# PSU2.net
KiCad netlist of a schematic drawn in Altium Designer
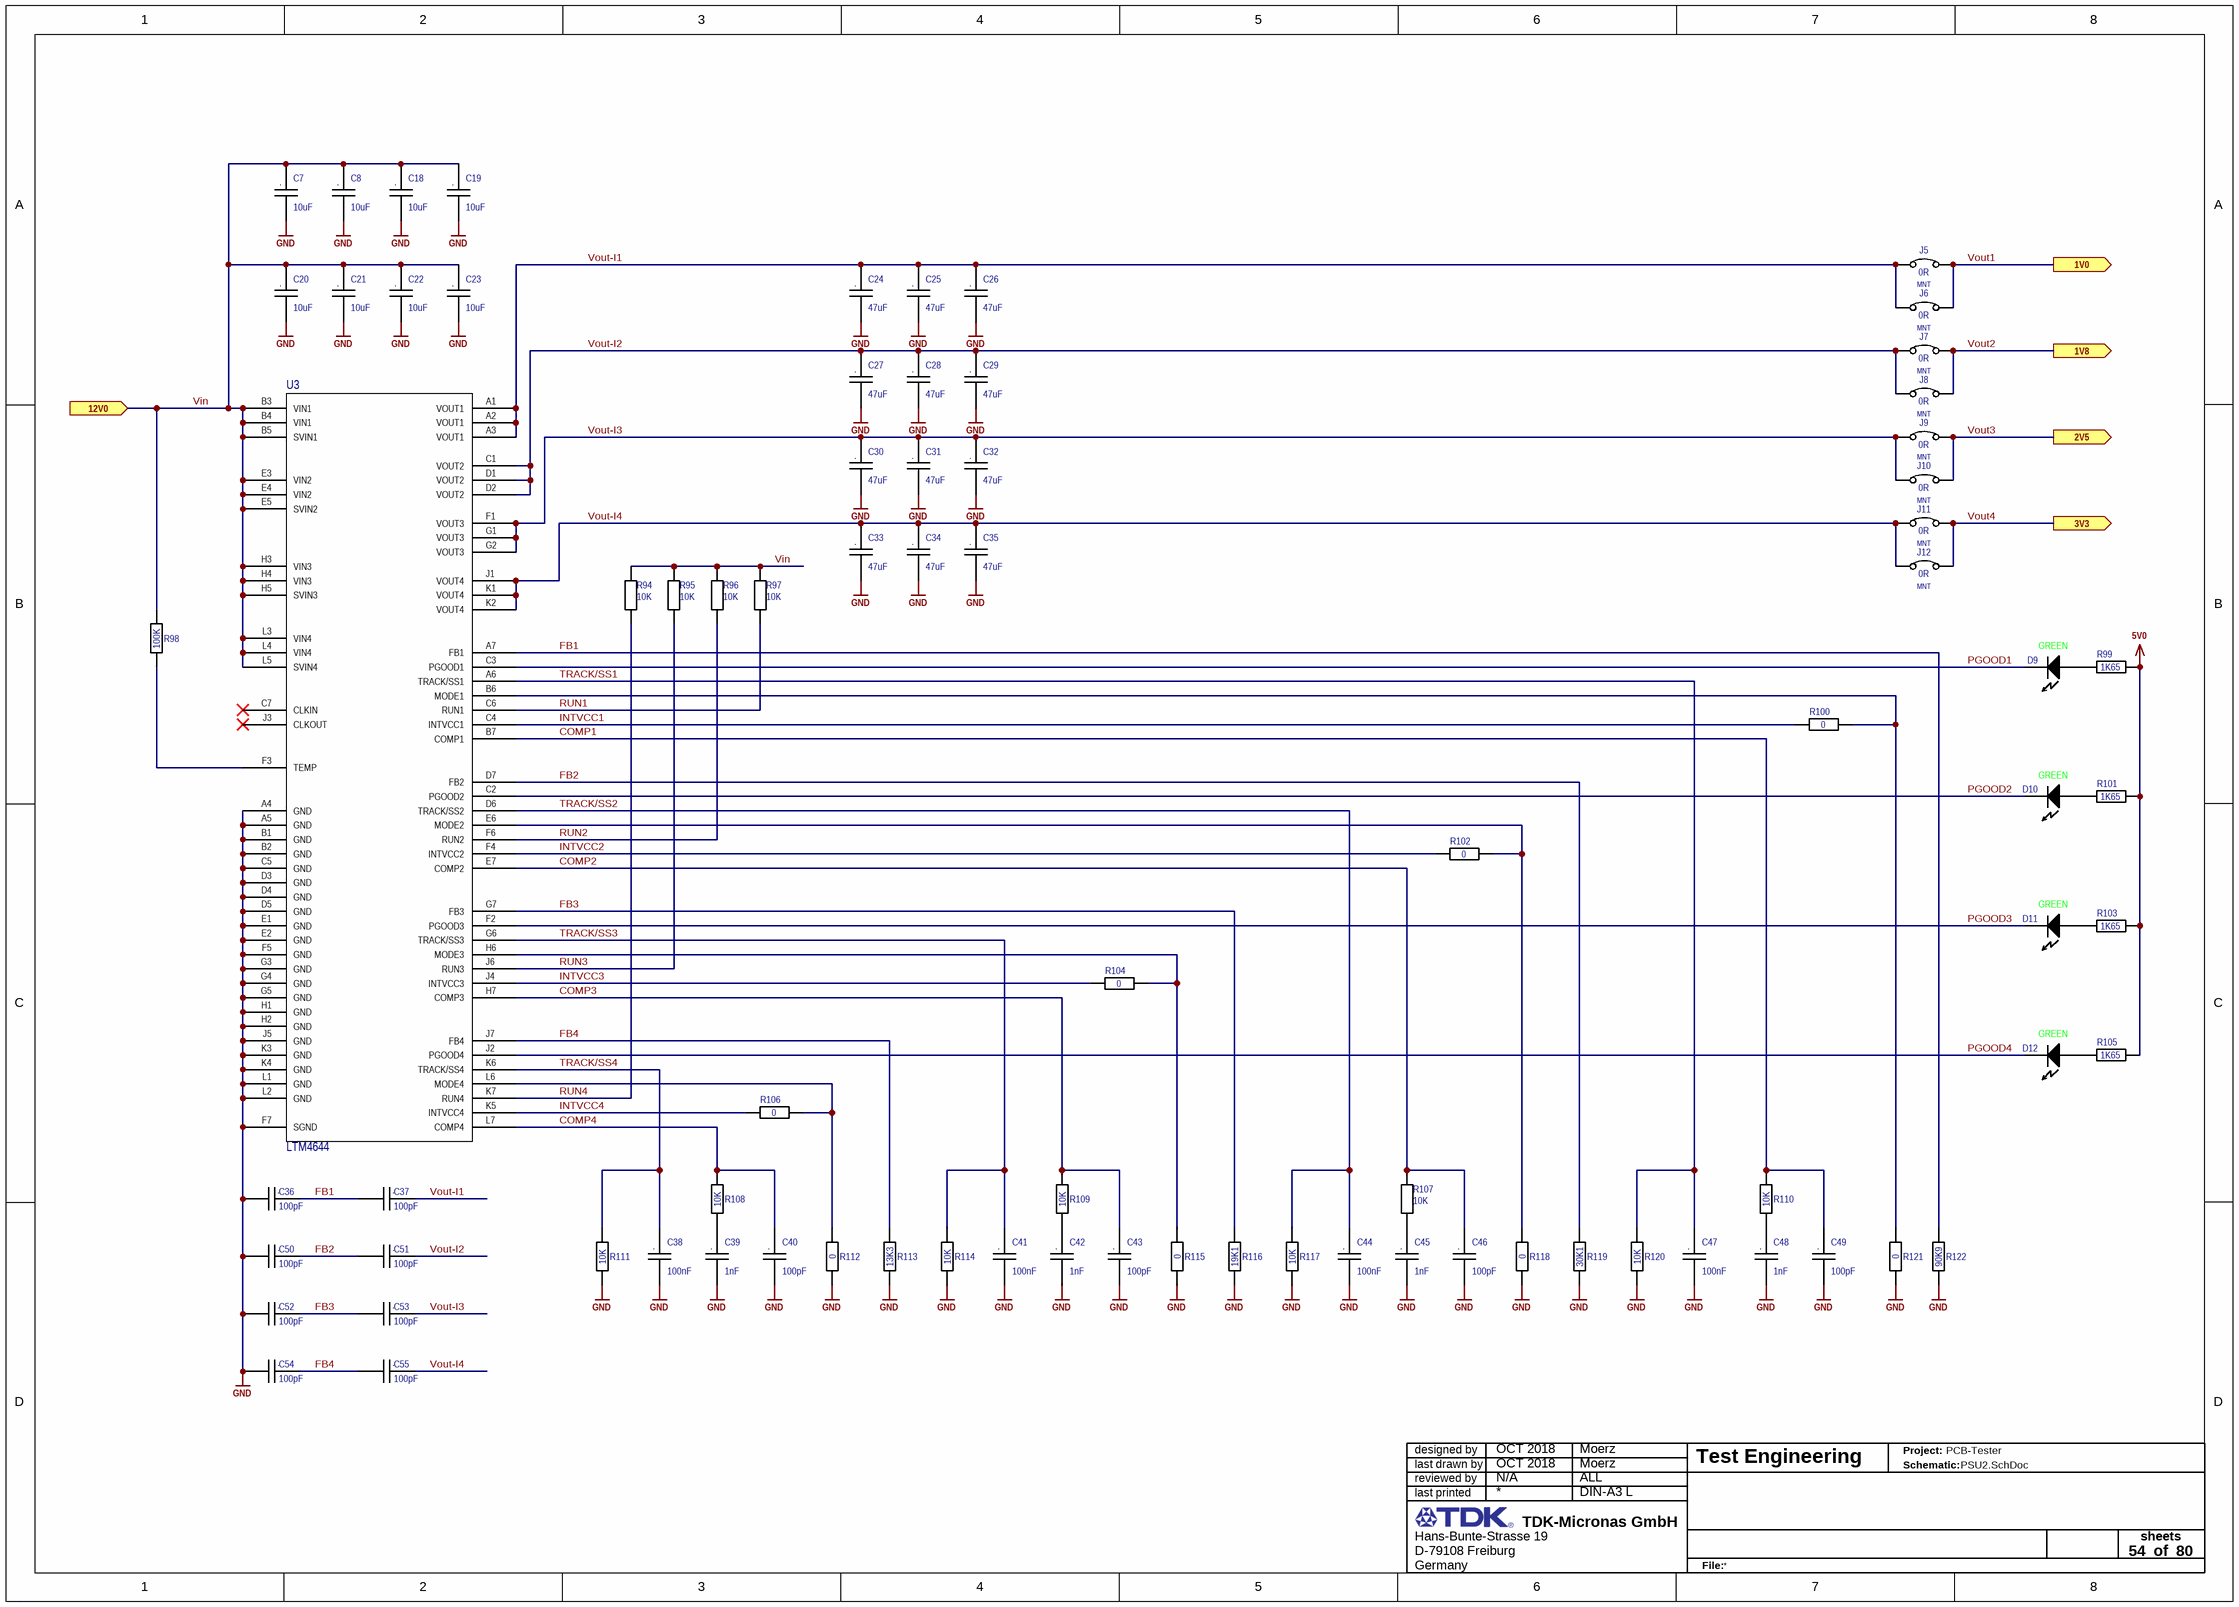
[diagram p0: PSU2.SchDoc]

(export (version "E")
  (design (tool "Eeschema 10.0.6"))
  (components
    (comp (ref "C7")
      (value "10uF")
      (footprint "C1206 Reflow")
      (description "CAP CER 10UF 25V X7R 1206")
      (fields
        (field (name "TOLERANCE") "±10%")
        (field (name "02. DISTRIBUTOR PART NUMBER") "445-7705-6-ND")
        (field (name "13. CREATED DATE/NAME") "AUG2018/Hören")
      )
      (libsource (lib "chickenfood") (part "C"))
    )
    (comp (ref "C8")
      (value "10uF")
      (footprint "C1206 Reflow")
      (description "CAP CER 10UF 25V X7R 1206")
      (fields
        (field (name "TOLERANCE") "±10%")
        (field (name "02. DISTRIBUTOR PART NUMBER") "445-7705-6-ND")
        (field (name "13. CREATED DATE/NAME") "AUG2018/Hören")
      )
      (libsource (lib "chickenfood") (part "C"))
    )
    (comp (ref "C18")
      (value "10uF")
      (footprint "C1206 Reflow")
      (description "CAP CER 10UF 25V X7R 1206")
      (fields
        (field (name "TOLERANCE") "±10%")
        (field (name "02. DISTRIBUTOR PART NUMBER") "445-7705-6-ND")
        (field (name "13. CREATED DATE/NAME") "AUG2018/Hören")
      )
      (libsource (lib "chickenfood") (part "C"))
    )
    (comp (ref "C19")
      (value "10uF")
      (footprint "C1206 Reflow")
      (description "CAP CER 10UF 25V X7R 1206")
      (fields
        (field (name "TOLERANCE") "±10%")
        (field (name "02. DISTRIBUTOR PART NUMBER") "445-7705-6-ND")
        (field (name "13. CREATED DATE/NAME") "AUG2018/Hören")
      )
      (libsource (lib "chickenfood") (part "C"))
    )
    (comp (ref "C20")
      (value "10uF")
      (footprint "C1206 Reflow")
      (description "CAP CER 10UF 25V X7R 1206")
      (fields
        (field (name "TOLERANCE") "±10%")
        (field (name "02. DISTRIBUTOR PART NUMBER") "445-7705-6-ND")
        (field (name "13. CREATED DATE/NAME") "AUG2018/Hören")
      )
      (libsource (lib "chickenfood") (part "C"))
    )
    (comp (ref "C21")
      (value "10uF")
      (footprint "C1206 Reflow")
      (description "CAP CER 10UF 25V X7R 1206")
      (fields
        (field (name "TOLERANCE") "±10%")
        (field (name "02. DISTRIBUTOR PART NUMBER") "445-7705-6-ND")
        (field (name "13. CREATED DATE/NAME") "AUG2018/Hören")
      )
      (libsource (lib "chickenfood") (part "C"))
    )
    (comp (ref "C22")
      (value "10uF")
      (footprint "C1206 Reflow")
      (description "CAP CER 10UF 25V X7R 1206")
      (fields
        (field (name "TOLERANCE") "±10%")
        (field (name "02. DISTRIBUTOR PART NUMBER") "445-7705-6-ND")
        (field (name "13. CREATED DATE/NAME") "AUG2018/Hören")
      )
      (libsource (lib "chickenfood") (part "C"))
    )
    (comp (ref "C23")
      (value "10uF")
      (footprint "C1206 Reflow")
      (description "CAP CER 10UF 25V X7R 1206")
      (fields
        (field (name "TOLERANCE") "±10%")
        (field (name "02. DISTRIBUTOR PART NUMBER") "445-7705-6-ND")
        (field (name "13. CREATED DATE/NAME") "AUG2018/Hören")
      )
      (libsource (lib "chickenfood") (part "C"))
    )
    (comp (ref "C24")
      (value "47uF")
      (footprint "C1210 Reflow")
      (description "CAP CER 47UF 10V X5R 1210")
      (fields
        (field (name "TOLERANCE") "±20%")
        (field (name "02. DISTRIBUTOR PART NUMBER") "1276-3380-6-ND")
        (field (name "13. CREATED DATE/NAME") "AUG2018/Hören")
      )
      (libsource (lib "chickenfood") (part "C"))
    )
    (comp (ref "C25")
      (value "47uF")
      (footprint "C1210 Reflow")
      (description "CAP CER 47UF 10V X5R 1210")
      (fields
        (field (name "TOLERANCE") "±20%")
        (field (name "02. DISTRIBUTOR PART NUMBER") "1276-3380-6-ND")
        (field (name "13. CREATED DATE/NAME") "AUG2018/Hören")
      )
      (libsource (lib "chickenfood") (part "C"))
    )
    (comp (ref "C26")
      (value "47uF")
      (footprint "C1210 Reflow")
      (description "CAP CER 47UF 10V X5R 1210")
      (fields
        (field (name "TOLERANCE") "±20%")
        (field (name "02. DISTRIBUTOR PART NUMBER") "1276-3380-6-ND")
        (field (name "13. CREATED DATE/NAME") "AUG2018/Hören")
      )
      (libsource (lib "chickenfood") (part "C"))
    )
    (comp (ref "C27")
      (value "47uF")
      (footprint "C1210 Reflow")
      (description "CAP CER 47UF 10V X5R 1210")
      (fields
        (field (name "TOLERANCE") "±20%")
        (field (name "02. DISTRIBUTOR PART NUMBER") "1276-3380-6-ND")
        (field (name "13. CREATED DATE/NAME") "AUG2018/Hören")
      )
      (libsource (lib "chickenfood") (part "C"))
    )
    (comp (ref "C28")
      (value "47uF")
      (footprint "C1210 Reflow")
      (description "CAP CER 47UF 10V X5R 1210")
      (fields
        (field (name "TOLERANCE") "±20%")
        (field (name "02. DISTRIBUTOR PART NUMBER") "1276-3380-6-ND")
        (field (name "13. CREATED DATE/NAME") "AUG2018/Hören")
      )
      (libsource (lib "chickenfood") (part "C"))
    )
    (comp (ref "C29")
      (value "47uF")
      (footprint "C1210 Reflow")
      (description "CAP CER 47UF 10V X5R 1210")
      (fields
        (field (name "TOLERANCE") "±20%")
        (field (name "02. DISTRIBUTOR PART NUMBER") "1276-3380-6-ND")
        (field (name "13. CREATED DATE/NAME") "AUG2018/Hören")
      )
      (libsource (lib "chickenfood") (part "C"))
    )
    (comp (ref "C30")
      (value "47uF")
      (footprint "C1210 Reflow")
      (description "CAP CER 47UF 10V X5R 1210")
      (fields
        (field (name "TOLERANCE") "±20%")
        (field (name "02. DISTRIBUTOR PART NUMBER") "1276-3380-6-ND")
        (field (name "13. CREATED DATE/NAME") "AUG2018/Hören")
      )
      (libsource (lib "chickenfood") (part "C"))
    )
    (comp (ref "C31")
      (value "47uF")
      (footprint "C1210 Reflow")
      (description "CAP CER 47UF 10V X5R 1210")
      (fields
        (field (name "TOLERANCE") "±20%")
        (field (name "02. DISTRIBUTOR PART NUMBER") "1276-3380-6-ND")
        (field (name "13. CREATED DATE/NAME") "AUG2018/Hören")
      )
      (libsource (lib "chickenfood") (part "C"))
    )
    (comp (ref "C32")
      (value "47uF")
      (footprint "C1210 Reflow")
      (description "CAP CER 47UF 10V X5R 1210")
      (fields
        (field (name "TOLERANCE") "±20%")
        (field (name "02. DISTRIBUTOR PART NUMBER") "1276-3380-6-ND")
        (field (name "13. CREATED DATE/NAME") "AUG2018/Hören")
      )
      (libsource (lib "chickenfood") (part "C"))
    )
    (comp (ref "C33")
      (value "47uF")
      (footprint "C1210 Reflow")
      (description "CAP CER 47UF 10V X5R 1210")
      (fields
        (field (name "TOLERANCE") "±20%")
        (field (name "02. DISTRIBUTOR PART NUMBER") "1276-3380-6-ND")
        (field (name "13. CREATED DATE/NAME") "AUG2018/Hören")
      )
      (libsource (lib "chickenfood") (part "C"))
    )
    (comp (ref "C34")
      (value "47uF")
      (footprint "C1210 Reflow")
      (description "CAP CER 47UF 10V X5R 1210")
      (fields
        (field (name "TOLERANCE") "±20%")
        (field (name "02. DISTRIBUTOR PART NUMBER") "1276-3380-6-ND")
        (field (name "13. CREATED DATE/NAME") "AUG2018/Hören")
      )
      (libsource (lib "chickenfood") (part "C"))
    )
    (comp (ref "C35")
      (value "47uF")
      (footprint "C1210 Reflow")
      (description "CAP CER 47UF 10V X5R 1210")
      (fields
        (field (name "TOLERANCE") "±20%")
        (field (name "02. DISTRIBUTOR PART NUMBER") "1276-3380-6-ND")
        (field (name "13. CREATED DATE/NAME") "AUG2018/Hören")
      )
      (libsource (lib "chickenfood") (part "C"))
    )
    (comp (ref "C36")
      (value "100pF")
      (footprint "C0402 Reflow")
      (description "CAP CER 100PF 25V C0G/NP0 0402")
      (fields
        (field (name "TOLERANCE") "±5%")
        (field (name "02. DISTRIBUTOR PART NUMBER") "399-1022-6-ND")
        (field (name "13. CREATED DATE/NAME") "AUG2018/Hören")
      )
      (libsource (lib "chickenfood") (part "C"))
    )
    (comp (ref "C37")
      (value "100pF")
      (footprint "C0402 Reflow")
      (description "CAP CER 100PF 25V C0G/NP0 0402")
      (fields
        (field (name "TOLERANCE") "±5%")
        (field (name "02. DISTRIBUTOR PART NUMBER") "399-1022-6-ND")
        (field (name "13. CREATED DATE/NAME") "AUG2018/Hören")
      )
      (libsource (lib "chickenfood") (part "C"))
    )
    (comp (ref "C38")
      (value "100nF")
      (footprint "C0402 Reflow")
      (description "CAP CER 0.1UF 25V X7R 0402")
      (fields
        (field (name "TOLERANCE") "±10%")
        (field (name "02. DISTRIBUTOR PART NUMBER") "311-2077-6-ND")
        (field (name "13. CREATED DATE/NAME") "AUG2018/Hören")
      )
      (libsource (lib "chickenfood") (part "C"))
    )
    (comp (ref "C39")
      (value "1nF")
      (footprint "C0402 Reflow")
      (description "CAP CER 1000PF 25V X7R 0402")
      (fields
        (field (name "TOLERANCE") "±10%")
        (field (name "02. DISTRIBUTOR PART NUMBER") "399-1031-6-ND")
        (field (name "13. CREATED DATE/NAME") "AUG2018/Hören")
      )
      (libsource (lib "chickenfood") (part "C"))
    )
    (comp (ref "C40")
      (value "100pF")
      (footprint "C0402 Reflow")
      (description "CAP CER 100PF 25V C0G/NP0 0402")
      (fields
        (field (name "TOLERANCE") "±5%")
        (field (name "02. DISTRIBUTOR PART NUMBER") "399-1022-6-ND")
        (field (name "13. CREATED DATE/NAME") "AUG2018/Hören")
      )
      (libsource (lib "chickenfood") (part "C"))
    )
    (comp (ref "C41")
      (value "100nF")
      (footprint "C0402 Reflow")
      (description "CAP CER 0.1UF 25V X7R 0402")
      (fields
        (field (name "TOLERANCE") "±10%")
        (field (name "02. DISTRIBUTOR PART NUMBER") "311-2077-6-ND")
        (field (name "13. CREATED DATE/NAME") "AUG2018/Hören")
      )
      (libsource (lib "chickenfood") (part "C"))
    )
    (comp (ref "C42")
      (value "1nF")
      (footprint "C0402 Reflow")
      (description "CAP CER 1000PF 25V X7R 0402")
      (fields
        (field (name "TOLERANCE") "±10%")
        (field (name "02. DISTRIBUTOR PART NUMBER") "399-1031-6-ND")
        (field (name "13. CREATED DATE/NAME") "AUG2018/Hören")
      )
      (libsource (lib "chickenfood") (part "C"))
    )
    (comp (ref "C43")
      (value "100pF")
      (footprint "C0402 Reflow")
      (description "CAP CER 100PF 25V C0G/NP0 0402")
      (fields
        (field (name "TOLERANCE") "±5%")
        (field (name "02. DISTRIBUTOR PART NUMBER") "399-1022-6-ND")
        (field (name "13. CREATED DATE/NAME") "AUG2018/Hören")
      )
      (libsource (lib "chickenfood") (part "C"))
    )
    (comp (ref "C44")
      (value "100nF")
      (footprint "C0402 Reflow")
      (description "CAP CER 0.1UF 25V X7R 0402")
      (fields
        (field (name "TOLERANCE") "±10%")
        (field (name "02. DISTRIBUTOR PART NUMBER") "311-2077-6-ND")
        (field (name "13. CREATED DATE/NAME") "AUG2018/Hören")
      )
      (libsource (lib "chickenfood") (part "C"))
    )
    (comp (ref "C45")
      (value "1nF")
      (footprint "C0402 Reflow")
      (description "CAP CER 1000PF 25V X7R 0402")
      (fields
        (field (name "TOLERANCE") "±10%")
        (field (name "02. DISTRIBUTOR PART NUMBER") "399-1031-6-ND")
        (field (name "13. CREATED DATE/NAME") "AUG2018/Hören")
      )
      (libsource (lib "chickenfood") (part "C"))
    )
    (comp (ref "C46")
      (value "100pF")
      (footprint "C0402 Reflow")
      (description "CAP CER 100PF 25V C0G/NP0 0402")
      (fields
        (field (name "TOLERANCE") "±5%")
        (field (name "02. DISTRIBUTOR PART NUMBER") "399-1022-6-ND")
        (field (name "13. CREATED DATE/NAME") "AUG2018/Hören")
      )
      (libsource (lib "chickenfood") (part "C"))
    )
    (comp (ref "C47")
      (value "100nF")
      (footprint "C0402 Reflow")
      (description "CAP CER 0.1UF 25V X7R 0402")
      (fields
        (field (name "TOLERANCE") "±10%")
        (field (name "02. DISTRIBUTOR PART NUMBER") "311-2077-6-ND")
        (field (name "13. CREATED DATE/NAME") "AUG2018/Hören")
      )
      (libsource (lib "chickenfood") (part "C"))
    )
    (comp (ref "C48")
      (value "1nF")
      (footprint "C0402 Reflow")
      (description "CAP CER 1000PF 25V X7R 0402")
      (fields
        (field (name "TOLERANCE") "±10%")
        (field (name "02. DISTRIBUTOR PART NUMBER") "399-1031-6-ND")
        (field (name "13. CREATED DATE/NAME") "AUG2018/Hören")
      )
      (libsource (lib "chickenfood") (part "C"))
    )
    (comp (ref "C49")
      (value "100pF")
      (footprint "C0402 Reflow")
      (description "CAP CER 100PF 25V C0G/NP0 0402")
      (fields
        (field (name "TOLERANCE") "±5%")
        (field (name "02. DISTRIBUTOR PART NUMBER") "399-1022-6-ND")
        (field (name "13. CREATED DATE/NAME") "AUG2018/Hören")
      )
      (libsource (lib "chickenfood") (part "C"))
    )
    (comp (ref "C50")
      (value "100pF")
      (footprint "C0402 Reflow")
      (description "CAP CER 100PF 25V C0G/NP0 0402")
      (fields
        (field (name "TOLERANCE") "±5%")
        (field (name "02. DISTRIBUTOR PART NUMBER") "399-1022-6-ND")
        (field (name "13. CREATED DATE/NAME") "AUG2018/Hören")
      )
      (libsource (lib "chickenfood") (part "C"))
    )
    (comp (ref "C51")
      (value "100pF")
      (footprint "C0402 Reflow")
      (description "CAP CER 100PF 25V C0G/NP0 0402")
      (fields
        (field (name "TOLERANCE") "±5%")
        (field (name "02. DISTRIBUTOR PART NUMBER") "399-1022-6-ND")
        (field (name "13. CREATED DATE/NAME") "AUG2018/Hören")
      )
      (libsource (lib "chickenfood") (part "C"))
    )
    (comp (ref "C52")
      (value "100pF")
      (footprint "C0402 Reflow")
      (description "CAP CER 100PF 25V C0G/NP0 0402")
      (fields
        (field (name "TOLERANCE") "±5%")
        (field (name "02. DISTRIBUTOR PART NUMBER") "399-1022-6-ND")
        (field (name "13. CREATED DATE/NAME") "AUG2018/Hören")
      )
      (libsource (lib "chickenfood") (part "C"))
    )
    (comp (ref "C53")
      (value "100pF")
      (footprint "C0402 Reflow")
      (description "CAP CER 100PF 25V C0G/NP0 0402")
      (fields
        (field (name "TOLERANCE") "±5%")
        (field (name "02. DISTRIBUTOR PART NUMBER") "399-1022-6-ND")
        (field (name "13. CREATED DATE/NAME") "AUG2018/Hören")
      )
      (libsource (lib "chickenfood") (part "C"))
    )
    (comp (ref "C54")
      (value "100pF")
      (footprint "C0402 Reflow")
      (description "CAP CER 100PF 25V C0G/NP0 0402")
      (fields
        (field (name "TOLERANCE") "±5%")
        (field (name "02. DISTRIBUTOR PART NUMBER") "399-1022-6-ND")
        (field (name "13. CREATED DATE/NAME") "AUG2018/Hören")
      )
      (libsource (lib "chickenfood") (part "C"))
    )
    (comp (ref "C55")
      (value "100pF")
      (footprint "C0402 Reflow")
      (description "CAP CER 100PF 25V C0G/NP0 0402")
      (fields
        (field (name "TOLERANCE") "±5%")
        (field (name "02. DISTRIBUTOR PART NUMBER") "399-1022-6-ND")
        (field (name "13. CREATED DATE/NAME") "AUG2018/Hören")
      )
      (libsource (lib "chickenfood") (part "C"))
    )
    (comp (ref "D9")
      (value "D")
      (footprint "L0603G")
      (description "LED GREEN DIFFUSED 0603 SMD")
      (fields
        (field (name "02. DISTRIBUTOR PART NUMBER") "475-2709-6-ND")
        (field (name "07. MANUFACTURER  PART NUMBER") "LG L29K-G2J1-24-Z")
        (field (name "COLOR") "GREEN")
        (field (name "13. CREATED DATE/NAME") "AUG2018/Hören")
      )
      (libsource (lib "chickenfood") (part "LED"))
    )
    (comp (ref "D10")
      (value "D")
      (footprint "L0603G")
      (description "LED GREEN DIFFUSED 0603 SMD")
      (fields
        (field (name "02. DISTRIBUTOR PART NUMBER") "475-2709-6-ND")
        (field (name "07. MANUFACTURER  PART NUMBER") "LG L29K-G2J1-24-Z")
        (field (name "COLOR") "GREEN")
        (field (name "13. CREATED DATE/NAME") "AUG2018/Hören")
      )
      (libsource (lib "chickenfood") (part "LED"))
    )
    (comp (ref "D11")
      (value "D")
      (footprint "L0603G")
      (description "LED GREEN DIFFUSED 0603 SMD")
      (fields
        (field (name "02. DISTRIBUTOR PART NUMBER") "475-2709-6-ND")
        (field (name "07. MANUFACTURER  PART NUMBER") "LG L29K-G2J1-24-Z")
        (field (name "COLOR") "GREEN")
        (field (name "13. CREATED DATE/NAME") "AUG2018/Hören")
      )
      (libsource (lib "chickenfood") (part "LED"))
    )
    (comp (ref "D12")
      (value "D")
      (footprint "L0603G")
      (description "LED GREEN DIFFUSED 0603 SMD")
      (fields
        (field (name "02. DISTRIBUTOR PART NUMBER") "475-2709-6-ND")
        (field (name "07. MANUFACTURER  PART NUMBER") "LG L29K-G2J1-24-Z")
        (field (name "COLOR") "GREEN")
        (field (name "13. CREATED DATE/NAME") "AUG2018/Hören")
      )
      (libsource (lib "chickenfood") (part "LED"))
    )
    (comp (ref "J5")
      (value "0R")
      (footprint "JumperSMD")
      (description "RES SMD 0 OHM JUMPER 1/10W 0603")
      (fields
        (field (name "02. DISTRIBUTOR PART NUMBER") "311-0.0GRDKR-ND")
        (field (name "07. MANUFACTURER  PART NUMBER") "RC0603JR-070RL")
        (field (name "POPULATED") "MNT")
      )
      (libsource (lib "chickenfood") (part "Jumper SMD"))
    )
    (comp (ref "J6")
      (value "0R")
      (footprint "JumperSMD")
      (description "RES SMD 0 OHM JUMPER 1/10W 0603")
      (fields
        (field (name "02. DISTRIBUTOR PART NUMBER") "311-0.0GRDKR-ND")
        (field (name "07. MANUFACTURER  PART NUMBER") "RC0603JR-070RL")
        (field (name "POPULATED") "MNT")
      )
      (libsource (lib "chickenfood") (part "Jumper SMD"))
    )
    (comp (ref "J7")
      (value "0R")
      (footprint "JumperSMD")
      (description "RES SMD 0 OHM JUMPER 1/10W 0603")
      (fields
        (field (name "02. DISTRIBUTOR PART NUMBER") "311-0.0GRDKR-ND")
        (field (name "07. MANUFACTURER  PART NUMBER") "RC0603JR-070RL")
        (field (name "POPULATED") "MNT")
      )
      (libsource (lib "chickenfood") (part "Jumper SMD"))
    )
    (comp (ref "J8")
      (value "0R")
      (footprint "JumperSMD")
      (description "RES SMD 0 OHM JUMPER 1/10W 0603")
      (fields
        (field (name "02. DISTRIBUTOR PART NUMBER") "311-0.0GRDKR-ND")
        (field (name "07. MANUFACTURER  PART NUMBER") "RC0603JR-070RL")
        (field (name "POPULATED") "MNT")
      )
      (libsource (lib "chickenfood") (part "Jumper SMD"))
    )
    (comp (ref "J9")
      (value "0R")
      (footprint "JumperSMD")
      (description "RES SMD 0 OHM JUMPER 1/10W 0603")
      (fields
        (field (name "02. DISTRIBUTOR PART NUMBER") "311-0.0GRDKR-ND")
        (field (name "07. MANUFACTURER  PART NUMBER") "RC0603JR-070RL")
        (field (name "POPULATED") "MNT")
      )
      (libsource (lib "chickenfood") (part "Jumper SMD"))
    )
    (comp (ref "J10")
      (value "0R")
      (footprint "JumperSMD")
      (description "RES SMD 0 OHM JUMPER 1/10W 0603")
      (fields
        (field (name "02. DISTRIBUTOR PART NUMBER") "311-0.0GRDKR-ND")
        (field (name "07. MANUFACTURER  PART NUMBER") "RC0603JR-070RL")
        (field (name "POPULATED") "MNT")
      )
      (libsource (lib "chickenfood") (part "Jumper SMD"))
    )
    (comp (ref "J11")
      (value "0R")
      (footprint "JumperSMD")
      (description "RES SMD 0 OHM JUMPER 1/10W 0603")
      (fields
        (field (name "02. DISTRIBUTOR PART NUMBER") "311-0.0GRDKR-ND")
        (field (name "07. MANUFACTURER  PART NUMBER") "RC0603JR-070RL")
        (field (name "POPULATED") "MNT")
      )
      (libsource (lib "chickenfood") (part "Jumper SMD"))
    )
    (comp (ref "J12")
      (value "0R")
      (footprint "JumperSMD")
      (description "RES SMD 0 OHM JUMPER 1/10W 0603")
      (fields
        (field (name "02. DISTRIBUTOR PART NUMBER") "311-0.0GRDKR-ND")
        (field (name "07. MANUFACTURER  PART NUMBER") "RC0603JR-070RL")
        (field (name "POPULATED") "MNT")
      )
      (libsource (lib "chickenfood") (part "Jumper SMD"))
    )
    (comp (ref "R94")
      (value "10K")
      (footprint "R0402 Reflow")
      (description "RES SMD 10K OHM 1% 1/16W 0402")
      (fields
        (field (name "TOLERANCE") "±1%")
        (field (name "02. DISTRIBUTOR PART NUMBER") "311-10.0KLRDKR-ND")
        (field (name "13. CREATED DATE/NAME") "AUG2018/Hören")
      )
      (libsource (lib "chickenfood") (part "R"))
    )
    (comp (ref "R95")
      (value "10K")
      (footprint "R0402 Reflow")
      (description "RES SMD 10K OHM 1% 1/16W 0402")
      (fields
        (field (name "TOLERANCE") "±1%")
        (field (name "02. DISTRIBUTOR PART NUMBER") "311-10.0KLRDKR-ND")
        (field (name "13. CREATED DATE/NAME") "AUG2018/Hören")
      )
      (libsource (lib "chickenfood") (part "R"))
    )
    (comp (ref "R96")
      (value "10K")
      (footprint "R0402 Reflow")
      (description "RES SMD 10K OHM 1% 1/16W 0402")
      (fields
        (field (name "TOLERANCE") "±1%")
        (field (name "02. DISTRIBUTOR PART NUMBER") "311-10.0KLRDKR-ND")
        (field (name "13. CREATED DATE/NAME") "AUG2018/Hören")
      )
      (libsource (lib "chickenfood") (part "R"))
    )
    (comp (ref "R97")
      (value "10K")
      (footprint "R0402 Reflow")
      (description "RES SMD 10K OHM 1% 1/16W 0402")
      (fields
        (field (name "TOLERANCE") "±1%")
        (field (name "02. DISTRIBUTOR PART NUMBER") "311-10.0KLRDKR-ND")
        (field (name "13. CREATED DATE/NAME") "AUG2018/Hören")
      )
      (libsource (lib "chickenfood") (part "R"))
    )
    (comp (ref "R98")
      (value "100K")
      (footprint "R0402 Reflow")
      (description "RES SMD 100K OHM 1% 1/16W 0402")
      (fields
        (field (name "TOLERANCE") "±1%")
        (field (name "02. DISTRIBUTOR PART NUMBER") "311-100KLRDKR-ND")
        (field (name "13. CREATED DATE/NAME") "AUG2018/Hören")
      )
      (libsource (lib "chickenfood") (part "R"))
    )
    (comp (ref "R99")
      (value "1K65")
      (footprint "R0402 Reflow")
      (description "RES SMD 1.65K OHM 1% 1/16W 0402")
      (fields
        (field (name "TOLERANCE") "±1%")
        (field (name "02. DISTRIBUTOR PART NUMBER") "YAG3043DKR-ND")
        (field (name "13. CREATED DATE/NAME") "AUG2018/Hören")
      )
      (libsource (lib "") (part "R_1"))
    )
    (comp (ref "R100")
      (value "0")
      (footprint "R0402 Reflow")
      (description "RES SMD 0 OHM JUMPER 1/16W 0402")
      (fields
        (field (name "02. DISTRIBUTOR PART NUMBER") "311-0.0JRDKR-ND")
        (field (name "07. MANUFACTURER  PART NUMBER") "RC0402JR-070RL")
        (field (name "13. CREATED DATE/NAME") "AUG2018/Hören")
      )
      (libsource (lib "") (part "R_2"))
    )
    (comp (ref "R101")
      (value "1K65")
      (footprint "R0402 Reflow")
      (description "RES SMD 1.65K OHM 1% 1/16W 0402")
      (fields
        (field (name "TOLERANCE") "±1%")
        (field (name "02. DISTRIBUTOR PART NUMBER") "YAG3043DKR-ND")
        (field (name "13. CREATED DATE/NAME") "AUG2018/Hören")
      )
      (libsource (lib "") (part "R_1"))
    )
    (comp (ref "R102")
      (value "0")
      (footprint "R0402 Reflow")
      (description "RES SMD 0 OHM JUMPER 1/16W 0402")
      (fields
        (field (name "02. DISTRIBUTOR PART NUMBER") "311-0.0JRDKR-ND")
        (field (name "07. MANUFACTURER  PART NUMBER") "RC0402JR-070RL")
        (field (name "13. CREATED DATE/NAME") "AUG2018/Hören")
      )
      (libsource (lib "") (part "R_2"))
    )
    (comp (ref "R103")
      (value "1K65")
      (footprint "R0402 Reflow")
      (description "RES SMD 1.65K OHM 1% 1/16W 0402")
      (fields
        (field (name "TOLERANCE") "±1%")
        (field (name "02. DISTRIBUTOR PART NUMBER") "YAG3043DKR-ND")
        (field (name "13. CREATED DATE/NAME") "AUG2018/Hören")
      )
      (libsource (lib "") (part "R_1"))
    )
    (comp (ref "R104")
      (value "0")
      (footprint "R0402 Reflow")
      (description "RES SMD 0 OHM JUMPER 1/16W 0402")
      (fields
        (field (name "02. DISTRIBUTOR PART NUMBER") "311-0.0JRDKR-ND")
        (field (name "07. MANUFACTURER  PART NUMBER") "RC0402JR-070RL")
        (field (name "13. CREATED DATE/NAME") "AUG2018/Hören")
      )
      (libsource (lib "") (part "R_2"))
    )
    (comp (ref "R105")
      (value "1K65")
      (footprint "R0402 Reflow")
      (description "RES SMD 1.65K OHM 1% 1/16W 0402")
      (fields
        (field (name "TOLERANCE") "±1%")
        (field (name "02. DISTRIBUTOR PART NUMBER") "YAG3043DKR-ND")
        (field (name "13. CREATED DATE/NAME") "AUG2018/Hören")
      )
      (libsource (lib "") (part "R_1"))
    )
    (comp (ref "R106")
      (value "0")
      (footprint "R0402 Reflow")
      (description "RES SMD 0 OHM JUMPER 1/16W 0402")
      (fields
        (field (name "02. DISTRIBUTOR PART NUMBER") "311-0.0JRDKR-ND")
        (field (name "07. MANUFACTURER  PART NUMBER") "RC0402JR-070RL")
        (field (name "13. CREATED DATE/NAME") "AUG2018/Hören")
      )
      (libsource (lib "") (part "R_2"))
    )
    (comp (ref "R107")
      (value "10K")
      (footprint "R0402 Reflow")
      (description "RES SMD 10K OHM 1% 1/16W 0402")
      (fields
        (field (name "TOLERANCE") "±1%")
        (field (name "02. DISTRIBUTOR PART NUMBER") "311-10.0KLRDKR-ND")
        (field (name "13. CREATED DATE/NAME") "AUG2018/Hören")
      )
      (libsource (lib "chickenfood") (part "R"))
    )
    (comp (ref "R108")
      (value "10K")
      (footprint "R0402 Reflow")
      (description "RES SMD 10K OHM 1% 1/16W 0402")
      (fields
        (field (name "TOLERANCE") "±1%")
        (field (name "02. DISTRIBUTOR PART NUMBER") "311-10.0KLRDKR-ND")
        (field (name "13. CREATED DATE/NAME") "AUG2018/Hören")
      )
      (libsource (lib "chickenfood") (part "R"))
    )
    (comp (ref "R109")
      (value "10K")
      (footprint "R0402 Reflow")
      (description "RES SMD 10K OHM 1% 1/16W 0402")
      (fields
        (field (name "TOLERANCE") "±1%")
        (field (name "02. DISTRIBUTOR PART NUMBER") "311-10.0KLRDKR-ND")
        (field (name "13. CREATED DATE/NAME") "AUG2018/Hören")
      )
      (libsource (lib "chickenfood") (part "R"))
    )
    (comp (ref "R110")
      (value "10K")
      (footprint "R0402 Reflow")
      (description "RES SMD 10K OHM 1% 1/16W 0402")
      (fields
        (field (name "TOLERANCE") "±1%")
        (field (name "02. DISTRIBUTOR PART NUMBER") "311-10.0KLRDKR-ND")
        (field (name "13. CREATED DATE/NAME") "AUG2018/Hören")
      )
      (libsource (lib "chickenfood") (part "R"))
    )
    (comp (ref "R111")
      (value "10K")
      (footprint "R0402 Reflow")
      (description "RES SMD 10K OHM 1% 1/16W 0402")
      (fields
        (field (name "TOLERANCE") "±1%")
        (field (name "02. DISTRIBUTOR PART NUMBER") "311-10.0KLRDKR-ND")
        (field (name "13. CREATED DATE/NAME") "AUG2018/Hören")
      )
      (libsource (lib "chickenfood") (part "R"))
    )
    (comp (ref "R112")
      (value "0")
      (footprint "R0402 Reflow")
      (description "RES SMD 0 OHM JUMPER 1/16W 0402")
      (fields
        (field (name "02. DISTRIBUTOR PART NUMBER") "311-0.0JRDKR-ND")
        (field (name "07. MANUFACTURER  PART NUMBER") "RC0402JR-070RL")
        (field (name "13. CREATED DATE/NAME") "AUG2018/Hören")
      )
      (libsource (lib "chickenfood") (part "R"))
    )
    (comp (ref "R113")
      (value "13K3")
      (footprint "R0402 Reflow")
      (description "RES SMD 13.3K OHM 1% 1/16W 0402")
      (fields
        (field (name "TOLERANCE") "±1%")
        (field (name "02. DISTRIBUTOR PART NUMBER") "YAG2974DKR-ND")
        (field (name "13. CREATED DATE/NAME") "AUG2018/Hören")
      )
      (libsource (lib "chickenfood") (part "R"))
    )
    (comp (ref "R114")
      (value "10K")
      (footprint "R0402 Reflow")
      (description "RES SMD 10K OHM 1% 1/16W 0402")
      (fields
        (field (name "TOLERANCE") "±1%")
        (field (name "02. DISTRIBUTOR PART NUMBER") "311-10.0KLRDKR-ND")
        (field (name "13. CREATED DATE/NAME") "AUG2018/Hören")
      )
      (libsource (lib "chickenfood") (part "R"))
    )
    (comp (ref "R115")
      (value "0")
      (footprint "R0402 Reflow")
      (description "RES SMD 0 OHM JUMPER 1/16W 0402")
      (fields
        (field (name "02. DISTRIBUTOR PART NUMBER") "311-0.0JRDKR-ND")
        (field (name "07. MANUFACTURER  PART NUMBER") "RC0402JR-070RL")
        (field (name "13. CREATED DATE/NAME") "AUG2018/Hören")
      )
      (libsource (lib "chickenfood") (part "R"))
    )
    (comp (ref "R116")
      (value "19K1")
      (footprint "R0402 Reflow")
      (description "RES SMD 19.1K OHM 1% 1/16W 0402")
      (fields
        (field (name "TOLERANCE") "±1%")
        (field (name "02. DISTRIBUTOR PART NUMBER") "311-19.1KLRDKR-ND")
        (field (name "13. CREATED DATE/NAME") "AUG2018/Hören")
      )
      (libsource (lib "chickenfood") (part "R"))
    )
    (comp (ref "R117")
      (value "10K")
      (footprint "R0402 Reflow")
      (description "RES SMD 10K OHM 1% 1/16W 0402")
      (fields
        (field (name "TOLERANCE") "±1%")
        (field (name "02. DISTRIBUTOR PART NUMBER") "311-10.0KLRDKR-ND")
        (field (name "13. CREATED DATE/NAME") "AUG2018/Hören")
      )
      (libsource (lib "chickenfood") (part "R"))
    )
    (comp (ref "R118")
      (value "0")
      (footprint "R0402 Reflow")
      (description "RES SMD 0 OHM JUMPER 1/16W 0402")
      (fields
        (field (name "02. DISTRIBUTOR PART NUMBER") "311-0.0JRDKR-ND")
        (field (name "07. MANUFACTURER  PART NUMBER") "RC0402JR-070RL")
        (field (name "13. CREATED DATE/NAME") "AUG2018/Hören")
      )
      (libsource (lib "chickenfood") (part "R"))
    )
    (comp (ref "R119")
      (value "30K1")
      (footprint "R0402 Reflow")
      (description "RES SMD 30.1K OHM 1% 1/16W 0402")
      (fields
        (field (name "TOLERANCE") "±1%")
        (field (name "02. DISTRIBUTOR PART NUMBER") "311-30.1KLRDKR-ND")
        (field (name "13. CREATED DATE/NAME") "AUG2018/Hören")
      )
      (libsource (lib "chickenfood") (part "R"))
    )
    (comp (ref "R120")
      (value "10K")
      (footprint "R0402 Reflow")
      (description "RES SMD 10K OHM 1% 1/16W 0402")
      (fields
        (field (name "TOLERANCE") "±1%")
        (field (name "02. DISTRIBUTOR PART NUMBER") "311-10.0KLRDKR-ND")
        (field (name "13. CREATED DATE/NAME") "AUG2018/Hören")
      )
      (libsource (lib "chickenfood") (part "R"))
    )
    (comp (ref "R121")
      (value "0")
      (footprint "R0402 Reflow")
      (description "RES SMD 0 OHM JUMPER 1/16W 0402")
      (fields
        (field (name "02. DISTRIBUTOR PART NUMBER") "311-0.0JRDKR-ND")
        (field (name "07. MANUFACTURER  PART NUMBER") "RC0402JR-070RL")
        (field (name "13. CREATED DATE/NAME") "AUG2018/Hören")
      )
      (libsource (lib "chickenfood") (part "R"))
    )
    (comp (ref "R122")
      (value "90K9")
      (footprint "R0402 Reflow")
      (description "RES SMD 90.9K OHM 1% 1/16W 0402")
      (fields
        (field (name "TOLERANCE") "±1%")
        (field (name "02. DISTRIBUTOR PART NUMBER") "311-90.9KLRDKR-ND")
        (field (name "13. CREATED DATE/NAME") "AUG2018/Hören")
      )
      (libsource (lib "chickenfood") (part "R"))
    )
    (comp (ref "U3")
      (value "U")
      (footprint "LTM4644")
      (description "DC DC CONVERTER 4X0.6-5.5V")
      (fields
        (field (name "MFR") "LINEAR TECHNOLOGY")
        (field (name "02. DISTRIBUTOR PART NUMBER") "LTM4644EY#PBF-ND")
        (field (name "NICNAME") "LTM4644")
      )
      (libsource (lib "tom") (part "LTM4644"))
    )
  )
  (nets
    (net (code "1") (name "/COMP1") (class "Default")
      (node (ref "C49") (pin "1") (pinfunction "1_1") (pintype "passive"))
      (node (ref "R110") (pin "2") (pinfunction "2_2") (pintype "passive"))
      (node (ref "U3") (pin "B7") (pinfunction "COMP1_B7") (pintype "passive"))
    )
    (net (code "2") (name "/COMP2") (class "Default")
      (node (ref "C46") (pin "1") (pinfunction "1_1") (pintype "passive"))
      (node (ref "R107") (pin "2") (pinfunction "2_2") (pintype "passive"))
      (node (ref "U3") (pin "E7") (pinfunction "COMP2_E7") (pintype "passive"))
    )
    (net (code "3") (name "/COMP3") (class "Default")
      (node (ref "C43") (pin "1") (pinfunction "1_1") (pintype "passive"))
      (node (ref "R109") (pin "2") (pinfunction "2_2") (pintype "passive"))
      (node (ref "U3") (pin "H7") (pinfunction "COMP3_H7") (pintype "passive"))
    )
    (net (code "4") (name "/COMP4") (class "Default")
      (node (ref "C40") (pin "1") (pinfunction "1_1") (pintype "passive"))
      (node (ref "R108") (pin "2") (pinfunction "2_2") (pintype "passive"))
      (node (ref "U3") (pin "L7") (pinfunction "COMP4_L7") (pintype "passive"))
    )
    (net (code "5") (name "/FB1") (class "Default")
      (node (ref "C36") (pin "1") (pinfunction "1_1") (pintype "passive"))
      (node (ref "C37") (pin "2") (pinfunction "2_2") (pintype "passive"))
      (node (ref "R122") (pin "2") (pinfunction "2_2") (pintype "passive"))
      (node (ref "U3") (pin "A7") (pinfunction "FB1_A7") (pintype "passive"))
    )
    (net (code "6") (name "/FB2") (class "Default")
      (node (ref "C50") (pin "1") (pinfunction "1_1") (pintype "passive"))
      (node (ref "C51") (pin "2") (pinfunction "2_2") (pintype "passive"))
      (node (ref "R119") (pin "2") (pinfunction "2_2") (pintype "passive"))
      (node (ref "U3") (pin "D7") (pinfunction "FB2_D7") (pintype "passive"))
    )
    (net (code "7") (name "/FB3") (class "Default")
      (node (ref "C52") (pin "1") (pinfunction "1_1") (pintype "passive"))
      (node (ref "C53") (pin "2") (pinfunction "2_2") (pintype "passive"))
      (node (ref "R116") (pin "2") (pinfunction "2_2") (pintype "passive"))
      (node (ref "U3") (pin "G7") (pinfunction "FB3_G7") (pintype "passive"))
    )
    (net (code "8") (name "/FB4") (class "Default")
      (node (ref "C54") (pin "1") (pinfunction "1_1") (pintype "passive"))
      (node (ref "C55") (pin "2") (pinfunction "2_2") (pintype "passive"))
      (node (ref "R113") (pin "2") (pinfunction "2_2") (pintype "passive"))
      (node (ref "U3") (pin "J7") (pinfunction "FB4_J7") (pintype "passive"))
    )
    (net (code "9") (name "/INTVCC1") (class "Default")
      (node (ref "R100") (pin "2") (pinfunction "2_2") (pintype "passive"))
      (node (ref "U3") (pin "C4") (pinfunction "INTVCC1_C4") (pintype "passive"))
    )
    (net (code "10") (name "/INTVCC2") (class "Default")
      (node (ref "R102") (pin "2") (pinfunction "2_2") (pintype "passive"))
      (node (ref "U3") (pin "F4") (pinfunction "INTVCC2_F4") (pintype "passive"))
    )
    (net (code "11") (name "/INTVCC3") (class "Default")
      (node (ref "R104") (pin "2") (pinfunction "2_2") (pintype "passive"))
      (node (ref "U3") (pin "J4") (pinfunction "INTVCC3_J4") (pintype "passive"))
    )
    (net (code "12") (name "/INTVCC4") (class "Default")
      (node (ref "R106") (pin "2") (pinfunction "2_2") (pintype "passive"))
      (node (ref "U3") (pin "K5") (pinfunction "INTVCC4_K5") (pintype "passive"))
    )
    (net (code "13") (name "/PGOOD1") (class "Default")
      (node (ref "D9") (pin "2") (pinfunction "Cathode_2") (pintype "passive"))
      (node (ref "U3") (pin "C3") (pinfunction "PGOOD1_C3") (pintype "passive"))
    )
    (net (code "14") (name "/PGOOD2") (class "Default")
      (node (ref "D10") (pin "2") (pinfunction "Cathode_2") (pintype "passive"))
      (node (ref "U3") (pin "C2") (pinfunction "PGOOD2_C2") (pintype "passive"))
    )
    (net (code "15") (name "/PGOOD3") (class "Default")
      (node (ref "D11") (pin "2") (pinfunction "Cathode_2") (pintype "passive"))
      (node (ref "U3") (pin "F2") (pinfunction "PGOOD3_F2") (pintype "passive"))
    )
    (net (code "16") (name "/PGOOD4") (class "Default")
      (node (ref "D12") (pin "2") (pinfunction "Cathode_2") (pintype "passive"))
      (node (ref "U3") (pin "J2") (pinfunction "PGOOD4_J2") (pintype "passive"))
    )
    (net (code "17") (name "/RUN1") (class "Default")
      (node (ref "R97") (pin "1") (pinfunction "1_1") (pintype "passive"))
      (node (ref "U3") (pin "C6") (pinfunction "RUN1_C6") (pintype "passive"))
    )
    (net (code "18") (name "/RUN2") (class "Default")
      (node (ref "R96") (pin "1") (pinfunction "1_1") (pintype "passive"))
      (node (ref "U3") (pin "F6") (pinfunction "RUN2_F6") (pintype "passive"))
    )
    (net (code "19") (name "/RUN3") (class "Default")
      (node (ref "R95") (pin "1") (pinfunction "1_1") (pintype "passive"))
      (node (ref "U3") (pin "J6") (pinfunction "RUN3_J6") (pintype "passive"))
    )
    (net (code "20") (name "/RUN4") (class "Default")
      (node (ref "R94") (pin "1") (pinfunction "1_1") (pintype "passive"))
      (node (ref "U3") (pin "K7") (pinfunction "RUN4_K7") (pintype "passive"))
    )
    (net (code "21") (name "/TRACK{slash}SS1") (class "Default")
      (node (ref "C47") (pin "1") (pinfunction "1_1") (pintype "passive"))
      (node (ref "R120") (pin "2") (pinfunction "2_2") (pintype "passive"))
      (node (ref "U3") (pin "A6") (pinfunction "TRACK/SS1_A6") (pintype "passive"))
    )
    (net (code "22") (name "/TRACK{slash}SS2") (class "Default")
      (node (ref "C44") (pin "1") (pinfunction "1_1") (pintype "passive"))
      (node (ref "R117") (pin "2") (pinfunction "2_2") (pintype "passive"))
      (node (ref "U3") (pin "D6") (pinfunction "TRACK/SS2_D6") (pintype "passive"))
    )
    (net (code "23") (name "/TRACK{slash}SS3") (class "Default")
      (node (ref "C41") (pin "1") (pinfunction "1_1") (pintype "passive"))
      (node (ref "R114") (pin "2") (pinfunction "2_2") (pintype "passive"))
      (node (ref "U3") (pin "G6") (pinfunction "TRACK/SS3_G6") (pintype "passive"))
    )
    (net (code "24") (name "/TRACK{slash}SS4") (class "Default")
      (node (ref "C38") (pin "1") (pinfunction "1_1") (pintype "passive"))
      (node (ref "R111") (pin "2") (pinfunction "2_2") (pintype "passive"))
      (node (ref "U3") (pin "K6") (pinfunction "TRACK/SS4_K6") (pintype "passive"))
    )
    (net (code "25") (name "/Vin") (class "Default")
      (node (ref "C18") (pin "1") (pinfunction "1_1") (pintype "passive"))
      (node (ref "C19") (pin "1") (pinfunction "1_1") (pintype "passive"))
      (node (ref "C20") (pin "1") (pinfunction "1_1") (pintype "passive"))
      (node (ref "C21") (pin "1") (pinfunction "1_1") (pintype "passive"))
      (node (ref "C22") (pin "1") (pinfunction "1_1") (pintype "passive"))
      (node (ref "C23") (pin "1") (pinfunction "1_1") (pintype "passive"))
      (node (ref "C7") (pin "1") (pinfunction "1_1") (pintype "passive"))
      (node (ref "C8") (pin "1") (pinfunction "1_1") (pintype "passive"))
      (node (ref "R94") (pin "2") (pinfunction "2_2") (pintype "passive"))
      (node (ref "R95") (pin "2") (pinfunction "2_2") (pintype "passive"))
      (node (ref "R96") (pin "2") (pinfunction "2_2") (pintype "passive"))
      (node (ref "R97") (pin "2") (pinfunction "2_2") (pintype "passive"))
      (node (ref "R98") (pin "2") (pinfunction "2_2") (pintype "passive"))
      (node (ref "U3") (pin "B3") (pinfunction "VIN1_B3") (pintype "passive"))
      (node (ref "U3") (pin "B4") (pinfunction "VIN1_B4") (pintype "passive"))
      (node (ref "U3") (pin "B5") (pinfunction "SVIN1_B5") (pintype "passive"))
      (node (ref "U3") (pin "E3") (pinfunction "VIN2_E3") (pintype "passive"))
      (node (ref "U3") (pin "E4") (pinfunction "VIN2_E4") (pintype "passive"))
      (node (ref "U3") (pin "E5") (pinfunction "SVIN2_E5") (pintype "passive"))
      (node (ref "U3") (pin "H3") (pinfunction "VIN3_H3") (pintype "passive"))
      (node (ref "U3") (pin "H4") (pinfunction "VIN3_H4") (pintype "passive"))
      (node (ref "U3") (pin "H5") (pinfunction "SVIN3_H5") (pintype "passive"))
      (node (ref "U3") (pin "L3") (pinfunction "VIN4_L3") (pintype "passive"))
      (node (ref "U3") (pin "L4") (pinfunction "VIN4_L4") (pintype "passive"))
      (node (ref "U3") (pin "L5") (pinfunction "SVIN4_L5") (pintype "passive"))
    )
    (net (code "26") (name "/Vout-I1") (class "Default")
      (node (ref "C24") (pin "1") (pinfunction "1_1") (pintype "passive"))
      (node (ref "C25") (pin "1") (pinfunction "1_1") (pintype "passive"))
      (node (ref "C26") (pin "1") (pinfunction "1_1") (pintype "passive"))
      (node (ref "C37") (pin "1") (pinfunction "1_1") (pintype "passive"))
      (node (ref "J5") (pin "1") (pinfunction "1_1") (pintype "passive"))
      (node (ref "J6") (pin "1") (pinfunction "1_1") (pintype "passive"))
      (node (ref "U3") (pin "A1") (pinfunction "VOUT1_A1") (pintype "passive"))
      (node (ref "U3") (pin "A2") (pinfunction "VOUT1_A2") (pintype "passive"))
      (node (ref "U3") (pin "A3") (pinfunction "VOUT1_A3") (pintype "passive"))
    )
    (net (code "27") (name "/Vout-I2") (class "Default")
      (node (ref "C27") (pin "1") (pinfunction "1_1") (pintype "passive"))
      (node (ref "C28") (pin "1") (pinfunction "1_1") (pintype "passive"))
      (node (ref "C29") (pin "1") (pinfunction "1_1") (pintype "passive"))
      (node (ref "C51") (pin "1") (pinfunction "1_1") (pintype "passive"))
      (node (ref "J7") (pin "1") (pinfunction "1_1") (pintype "passive"))
      (node (ref "J8") (pin "1") (pinfunction "1_1") (pintype "passive"))
      (node (ref "U3") (pin "C1") (pinfunction "VOUT2_C1") (pintype "passive"))
      (node (ref "U3") (pin "D1") (pinfunction "VOUT2_D1") (pintype "passive"))
      (node (ref "U3") (pin "D2") (pinfunction "VOUT2_D2") (pintype "passive"))
    )
    (net (code "28") (name "/Vout-I3") (class "Default")
      (node (ref "C30") (pin "1") (pinfunction "1_1") (pintype "passive"))
      (node (ref "C31") (pin "1") (pinfunction "1_1") (pintype "passive"))
      (node (ref "C32") (pin "1") (pinfunction "1_1") (pintype "passive"))
      (node (ref "C53") (pin "1") (pinfunction "1_1") (pintype "passive"))
      (node (ref "J10") (pin "1") (pinfunction "1_1") (pintype "passive"))
      (node (ref "J9") (pin "1") (pinfunction "1_1") (pintype "passive"))
      (node (ref "U3") (pin "F1") (pinfunction "VOUT3_F1") (pintype "passive"))
      (node (ref "U3") (pin "G1") (pinfunction "VOUT3_G1") (pintype "passive"))
      (node (ref "U3") (pin "G2") (pinfunction "VOUT3_G2") (pintype "passive"))
    )
    (net (code "29") (name "/Vout-I4") (class "Default")
      (node (ref "C33") (pin "1") (pinfunction "1_1") (pintype "passive"))
      (node (ref "C34") (pin "1") (pinfunction "1_1") (pintype "passive"))
      (node (ref "C35") (pin "1") (pinfunction "1_1") (pintype "passive"))
      (node (ref "C55") (pin "1") (pinfunction "1_1") (pintype "passive"))
      (node (ref "J11") (pin "1") (pinfunction "1_1") (pintype "passive"))
      (node (ref "J12") (pin "1") (pinfunction "1_1") (pintype "passive"))
      (node (ref "U3") (pin "J1") (pinfunction "VOUT4_J1") (pintype "passive"))
      (node (ref "U3") (pin "K1") (pinfunction "VOUT4_K1") (pintype "passive"))
      (node (ref "U3") (pin "K2") (pinfunction "VOUT4_K2") (pintype "passive"))
    )
    (net (code "30") (name "/Vout1") (class "Default")
      (node (ref "J5") (pin "2") (pinfunction "2_2") (pintype "passive"))
      (node (ref "J6") (pin "2") (pinfunction "2_2") (pintype "passive"))
    )
    (net (code "31") (name "/Vout2") (class "Default")
      (node (ref "J7") (pin "2") (pinfunction "2_2") (pintype "passive"))
      (node (ref "J8") (pin "2") (pinfunction "2_2") (pintype "passive"))
    )
    (net (code "32") (name "/Vout3") (class "Default")
      (node (ref "J10") (pin "2") (pinfunction "2_2") (pintype "passive"))
      (node (ref "J9") (pin "2") (pinfunction "2_2") (pintype "passive"))
    )
    (net (code "33") (name "/Vout4") (class "Default")
      (node (ref "J11") (pin "2") (pinfunction "2_2") (pintype "passive"))
      (node (ref "J12") (pin "2") (pinfunction "2_2") (pintype "passive"))
    )
    (net (code "34") (name "5V0") (class "Default")
      (node (ref "R101") (pin "2") (pinfunction "2_2") (pintype "passive"))
      (node (ref "R103") (pin "2") (pinfunction "2_2") (pintype "passive"))
      (node (ref "R105") (pin "2") (pinfunction "2_2") (pintype "passive"))
      (node (ref "R99") (pin "2") (pinfunction "2_2") (pintype "passive"))
    )
    (net (code "35") (name "GND") (class "Default")
      (node (ref "C18") (pin "2") (pinfunction "2_2") (pintype "passive"))
      (node (ref "C19") (pin "2") (pinfunction "2_2") (pintype "passive"))
      (node (ref "C20") (pin "2") (pinfunction "2_2") (pintype "passive"))
      (node (ref "C21") (pin "2") (pinfunction "2_2") (pintype "passive"))
      (node (ref "C22") (pin "2") (pinfunction "2_2") (pintype "passive"))
      (node (ref "C23") (pin "2") (pinfunction "2_2") (pintype "passive"))
      (node (ref "C24") (pin "2") (pinfunction "2_2") (pintype "passive"))
      (node (ref "C25") (pin "2") (pinfunction "2_2") (pintype "passive"))
      (node (ref "C26") (pin "2") (pinfunction "2_2") (pintype "passive"))
      (node (ref "C27") (pin "2") (pinfunction "2_2") (pintype "passive"))
      (node (ref "C28") (pin "2") (pinfunction "2_2") (pintype "passive"))
      (node (ref "C29") (pin "2") (pinfunction "2_2") (pintype "passive"))
      (node (ref "C30") (pin "2") (pinfunction "2_2") (pintype "passive"))
      (node (ref "C31") (pin "2") (pinfunction "2_2") (pintype "passive"))
      (node (ref "C32") (pin "2") (pinfunction "2_2") (pintype "passive"))
      (node (ref "C33") (pin "2") (pinfunction "2_2") (pintype "passive"))
      (node (ref "C34") (pin "2") (pinfunction "2_2") (pintype "passive"))
      (node (ref "C35") (pin "2") (pinfunction "2_2") (pintype "passive"))
      (node (ref "C36") (pin "2") (pinfunction "2_2") (pintype "passive"))
      (node (ref "C38") (pin "2") (pinfunction "2_2") (pintype "passive"))
      (node (ref "C39") (pin "2") (pinfunction "2_2") (pintype "passive"))
      (node (ref "C40") (pin "2") (pinfunction "2_2") (pintype "passive"))
      (node (ref "C41") (pin "2") (pinfunction "2_2") (pintype "passive"))
      (node (ref "C42") (pin "2") (pinfunction "2_2") (pintype "passive"))
      (node (ref "C43") (pin "2") (pinfunction "2_2") (pintype "passive"))
      (node (ref "C44") (pin "2") (pinfunction "2_2") (pintype "passive"))
      (node (ref "C45") (pin "2") (pinfunction "2_2") (pintype "passive"))
      (node (ref "C46") (pin "2") (pinfunction "2_2") (pintype "passive"))
      (node (ref "C47") (pin "2") (pinfunction "2_2") (pintype "passive"))
      (node (ref "C48") (pin "2") (pinfunction "2_2") (pintype "passive"))
      (node (ref "C49") (pin "2") (pinfunction "2_2") (pintype "passive"))
      (node (ref "C50") (pin "2") (pinfunction "2_2") (pintype "passive"))
      (node (ref "C52") (pin "2") (pinfunction "2_2") (pintype "passive"))
      (node (ref "C54") (pin "2") (pinfunction "2_2") (pintype "passive"))
      (node (ref "C7") (pin "2") (pinfunction "2_2") (pintype "passive"))
      (node (ref "C8") (pin "2") (pinfunction "2_2") (pintype "passive"))
      (node (ref "R111") (pin "1") (pinfunction "1_1") (pintype "passive"))
      (node (ref "R112") (pin "1") (pinfunction "1_1") (pintype "passive"))
      (node (ref "R113") (pin "1") (pinfunction "1_1") (pintype "passive"))
      (node (ref "R114") (pin "1") (pinfunction "1_1") (pintype "passive"))
      (node (ref "R115") (pin "1") (pinfunction "1_1") (pintype "passive"))
      (node (ref "R116") (pin "1") (pinfunction "1_1") (pintype "passive"))
      (node (ref "R117") (pin "1") (pinfunction "1_1") (pintype "passive"))
      (node (ref "R118") (pin "1") (pinfunction "1_1") (pintype "passive"))
      (node (ref "R119") (pin "1") (pinfunction "1_1") (pintype "passive"))
      (node (ref "R120") (pin "1") (pinfunction "1_1") (pintype "passive"))
      (node (ref "R121") (pin "1") (pinfunction "1_1") (pintype "passive"))
      (node (ref "R122") (pin "1") (pinfunction "1_1") (pintype "passive"))
      (node (ref "U3") (pin "A4") (pinfunction "GND_A4") (pintype "passive"))
      (node (ref "U3") (pin "A5") (pinfunction "GND_A5") (pintype "passive"))
      (node (ref "U3") (pin "B1") (pinfunction "GND_B1") (pintype "passive"))
      (node (ref "U3") (pin "B2") (pinfunction "GND_B2") (pintype "passive"))
      (node (ref "U3") (pin "C5") (pinfunction "GND_C5") (pintype "passive"))
      (node (ref "U3") (pin "D3") (pinfunction "GND_D3") (pintype "passive"))
      (node (ref "U3") (pin "D4") (pinfunction "GND_D4") (pintype "passive"))
      (node (ref "U3") (pin "D5") (pinfunction "GND_D5") (pintype "passive"))
      (node (ref "U3") (pin "E1") (pinfunction "GND_E1") (pintype "passive"))
      (node (ref "U3") (pin "E2") (pinfunction "GND_E2") (pintype "passive"))
      (node (ref "U3") (pin "F5") (pinfunction "GND_F5") (pintype "passive"))
      (node (ref "U3") (pin "F7") (pinfunction "SGND_F7") (pintype "passive"))
      (node (ref "U3") (pin "G3") (pinfunction "GND_G3") (pintype "passive"))
      (node (ref "U3") (pin "G4") (pinfunction "GND_G4") (pintype "passive"))
      (node (ref "U3") (pin "G5") (pinfunction "GND_G5") (pintype "passive"))
      (node (ref "U3") (pin "H1") (pinfunction "GND_H1") (pintype "passive"))
      (node (ref "U3") (pin "H2") (pinfunction "GND_H2") (pintype "passive"))
      (node (ref "U3") (pin "J5") (pinfunction "GND_J5") (pintype "passive"))
      (node (ref "U3") (pin "K3") (pinfunction "GND_K3") (pintype "passive"))
      (node (ref "U3") (pin "K4") (pinfunction "GND_K4") (pintype "passive"))
      (node (ref "U3") (pin "L1") (pinfunction "GND_L1") (pintype "passive"))
      (node (ref "U3") (pin "L2") (pinfunction "GND_L2") (pintype "passive"))
    )
    (net (code "36") (name "Net-(C39-Pad1)") (class "Default")
      (node (ref "C39") (pin "1") (pinfunction "1_1") (pintype "passive"))
      (node (ref "R108") (pin "1") (pinfunction "1_1") (pintype "passive"))
    )
    (net (code "37") (name "Net-(C42-Pad1)") (class "Default")
      (node (ref "C42") (pin "1") (pinfunction "1_1") (pintype "passive"))
      (node (ref "R109") (pin "1") (pinfunction "1_1") (pintype "passive"))
    )
    (net (code "38") (name "Net-(C45-Pad1)") (class "Default")
      (node (ref "C45") (pin "1") (pinfunction "1_1") (pintype "passive"))
      (node (ref "R107") (pin "1") (pinfunction "1_1") (pintype "passive"))
    )
    (net (code "39") (name "Net-(C48-Pad1)") (class "Default")
      (node (ref "C48") (pin "1") (pinfunction "1_1") (pintype "passive"))
      (node (ref "R110") (pin "1") (pinfunction "1_1") (pintype "passive"))
    )
    (net (code "40") (name "Net-(D9-Anode)") (class "Default")
      (node (ref "D9") (pin "1") (pinfunction "Anode_1") (pintype "passive"))
      (node (ref "R99") (pin "1") (pinfunction "1_1") (pintype "passive"))
    )
    (net (code "41") (name "Net-(D10-Anode)") (class "Default")
      (node (ref "D10") (pin "1") (pinfunction "Anode_1") (pintype "passive"))
      (node (ref "R101") (pin "1") (pinfunction "1_1") (pintype "passive"))
    )
    (net (code "42") (name "Net-(D11-Anode)") (class "Default")
      (node (ref "D11") (pin "1") (pinfunction "Anode_1") (pintype "passive"))
      (node (ref "R103") (pin "1") (pinfunction "1_1") (pintype "passive"))
    )
    (net (code "43") (name "Net-(D12-Anode)") (class "Default")
      (node (ref "D12") (pin "1") (pinfunction "Anode_1") (pintype "passive"))
      (node (ref "R105") (pin "1") (pinfunction "1_1") (pintype "passive"))
    )
    (net (code "44") (name "Net-(U3-MODE1)") (class "Default")
      (node (ref "R100") (pin "1") (pinfunction "1_1") (pintype "passive"))
      (node (ref "R121") (pin "2") (pinfunction "2_2") (pintype "passive"))
      (node (ref "U3") (pin "B6") (pinfunction "MODE1_B6") (pintype "passive"))
    )
    (net (code "45") (name "Net-(U3-MODE2)") (class "Default")
      (node (ref "R102") (pin "1") (pinfunction "1_1") (pintype "passive"))
      (node (ref "R118") (pin "2") (pinfunction "2_2") (pintype "passive"))
      (node (ref "U3") (pin "E6") (pinfunction "MODE2_E6") (pintype "passive"))
    )
    (net (code "46") (name "Net-(U3-MODE3)") (class "Default")
      (node (ref "R104") (pin "1") (pinfunction "1_1") (pintype "passive"))
      (node (ref "R115") (pin "2") (pinfunction "2_2") (pintype "passive"))
      (node (ref "U3") (pin "H6") (pinfunction "MODE3_H6") (pintype "passive"))
    )
    (net (code "47") (name "Net-(U3-MODE4)") (class "Default")
      (node (ref "R106") (pin "1") (pinfunction "1_1") (pintype "passive"))
      (node (ref "R112") (pin "2") (pinfunction "2_2") (pintype "passive"))
      (node (ref "U3") (pin "L6") (pinfunction "MODE4_L6") (pintype "passive"))
    )
    (net (code "48") (name "Net-(U3-TEMP)") (class "Default")
      (node (ref "R98") (pin "1") (pinfunction "1_1") (pintype "passive"))
      (node (ref "U3") (pin "F3") (pinfunction "TEMP_F3") (pintype "passive"))
    )
    (net (code "49") (name "unconnected-(U3-CLKIN-PadC7)") (class "Default")
      (node (ref "U3") (pin "C7") (pinfunction "CLKIN_C7") (pintype "passive+no_connect"))
    )
    (net (code "50") (name "unconnected-(U3-CLKOUT-PadJ3)") (class "Default")
      (node (ref "U3") (pin "J3") (pinfunction "CLKOUT_J3") (pintype "passive+no_connect"))
    )
  )
)
